# DM.net
KiCad netlist of a schematic drawn in Altium Designer
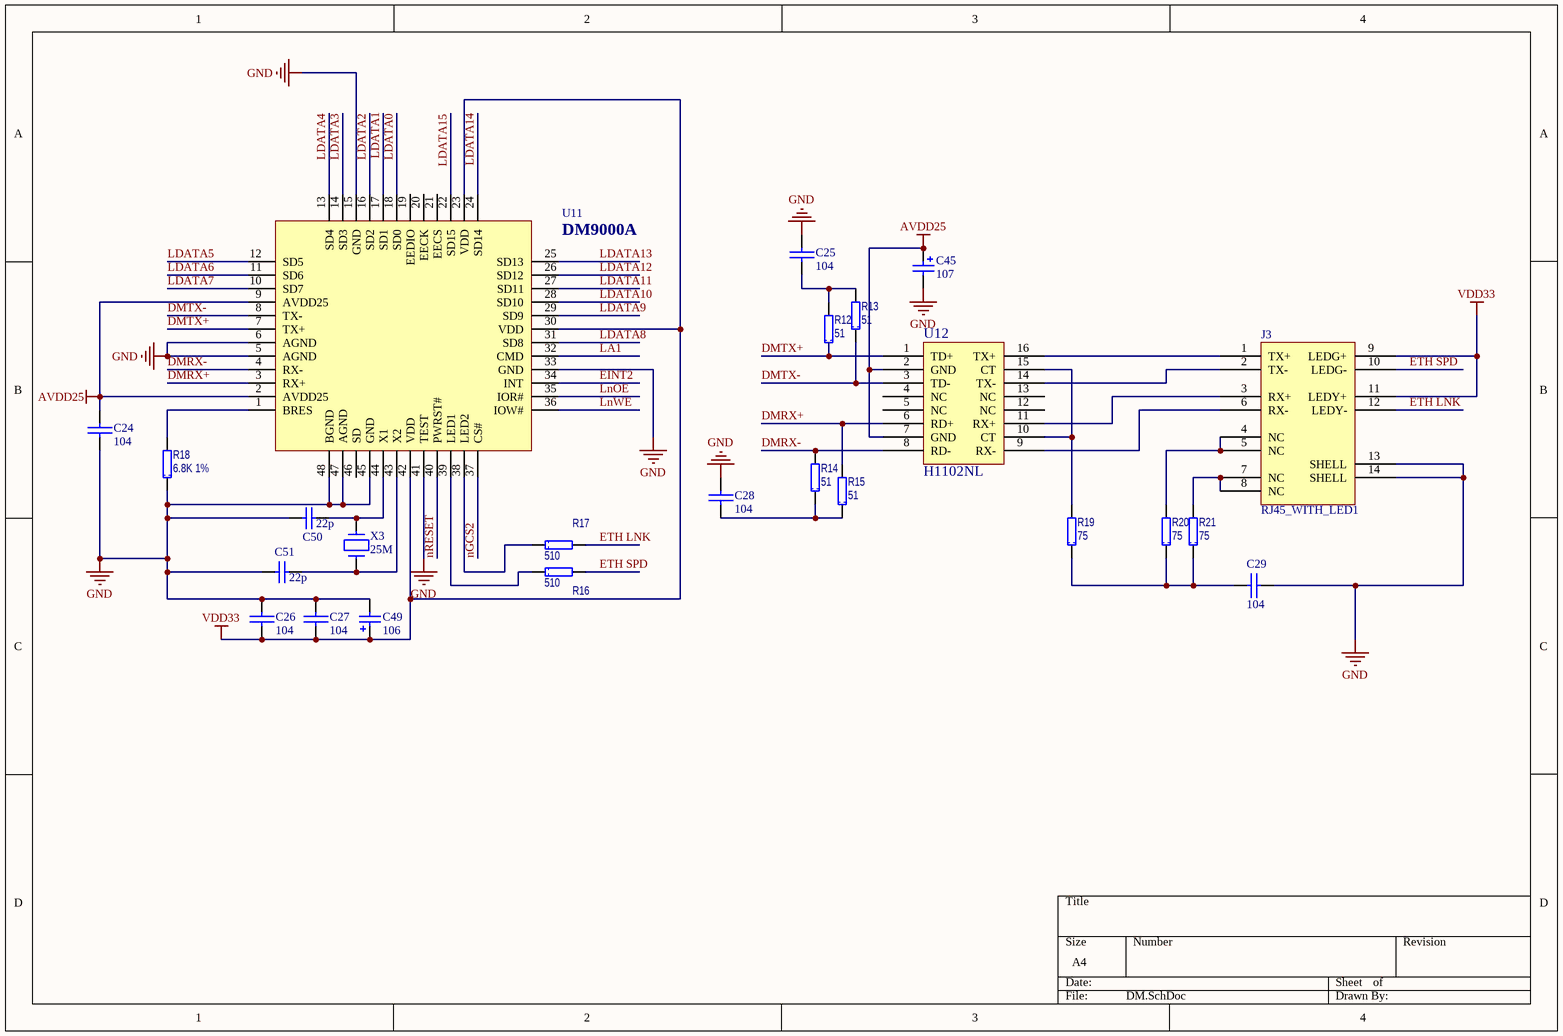
[diagram p0: DM.SchDoc]

(export (version "E")
  (design (tool "Eeschema 10.0.6"))
  (components
    (comp (ref "C24") (value "104") (footprint "0603A") (libsource (lib "ARM_DEMO") (part "CAP_3")))
    (comp (ref "C25")
      (value "104")
      (footprint "0603A")
      (description "Capacitor")
      (libsource (lib "ARM_DEMO") (part "CAP_2"))
    )
    (comp (ref "C26")
      (value "104")
      (footprint "A型钽电容")
      (description "Capacitor")
      (libsource (lib "ARM_DEMO") (part "CAP_1"))
    )
    (comp (ref "C27")
      (value "104")
      (footprint "A型钽电容")
      (description "Capacitor")
      (libsource (lib "ARM_DEMO") (part "CAP_1"))
    )
    (comp (ref "C28")
      (value "104")
      (footprint "0603A")
      (description "Capacitor")
      (libsource (lib "ARM_DEMO") (part "CAP_2"))
    )
    (comp (ref "C29")
      (value "104")
      (footprint "A型钽电容")
      (description "Capacitor")
      (libsource (lib "ARM_DEMO") (part "CAP_1"))
    )
    (comp (ref "C45")
      (value "107")
      (footprint "POLAR0.8")
      (description "Polarized Capacitor (Axial)")
      (fields (field (name "Comment") "Cap Pol2") (field (name "PUBLISHER") "Altium Limited"))
      (libsource (lib "Miscellaneous Devices") (part "Cap Pol2"))
    )
    (comp (ref "C49")
      (value "106")
      (footprint "POLAR0.8")
      (description "Polarized Capacitor (Axial)")
      (fields (field (name "Comment") "Cap Pol2") (field (name "PUBLISHER") "Altium Limited"))
      (libsource (lib "Miscellaneous Devices") (part "Cap Pol2"))
    )
    (comp (ref "C50")
      (value "22p")
      (footprint "3225")
      (description "Capacitor")
      (fields (field (name "Comment") "Cap") (field (name "PUBLISHER") "Altium Limited"))
      (libsource (lib "ARM_DEMO") (part "Cap"))
    )
    (comp (ref "C51")
      (value "22p")
      (footprint "3225")
      (description "Capacitor")
      (fields (field (name "Comment") "Cap") (field (name "PUBLISHER") "Altium Limited"))
      (libsource (lib "ARM_DEMO") (part "Cap"))
    )
    (comp (ref "J3")
      (value "RJ45_WITH_LED1")
      (footprint "RJ45")
      (libsource (lib "mySchlib") (part "RJ45_WITH_LED1"))
    )
    (comp (ref "R12") (value "51") (footprint "0603R") (libsource (lib "ARM_DEMO") (part "RES")))
    (comp (ref "R13") (value "51") (footprint "0603R") (libsource (lib "ARM_DEMO") (part "RES")))
    (comp (ref "R14") (value "51") (footprint "0603R") (libsource (lib "ARM_DEMO") (part "RES")))
    (comp (ref "R15") (value "51") (footprint "0603R") (libsource (lib "ARM_DEMO") (part "RES")))
    (comp (ref "R16") (value "510") (footprint "0603R") (libsource (lib "ARM_DEMO") (part "RES")))
    (comp (ref "R17") (value "510") (footprint "0603R") (libsource (lib "ARM_DEMO") (part "RES")))
    (comp (ref "R18") (value "6.8K 1%") (footprint "0603R") (libsource (lib "ARM_DEMO") (part "RES")))
    (comp (ref "R19") (value "75") (footprint "0603R") (libsource (lib "ARM_DEMO") (part "RES")))
    (comp (ref "R20") (value "75") (footprint "0603R") (libsource (lib "ARM_DEMO") (part "RES")))
    (comp (ref "R21") (value "75") (footprint "0603R") (libsource (lib "ARM_DEMO") (part "RES")))
    (comp (ref "U11")
      (value "DM9000A")
      (footprint "LQFP-48_M")
      (description "网络芯片")
      (libsource (lib "ARM_DEMO") (part "DM9000A"))
    )
    (comp (ref "U12") (value "H1102NL") (footprint "H1102") (libsource (lib "ARM_DEMO") (part "H1012")))
    (comp (ref "X3") (value "25M") (footprint "OSC2PR-1") (libsource (lib "ARM_DEMO") (part "CRYSTAL_2")))
  )
  (nets
    (net (code "1") (name "/DMRX+") (class "Default")
      (node (ref "R15") (pin "2") (pinfunction "2_2") (pintype "passive"))
      (node (ref "U11") (pin "3") (pinfunction "RX+_3") (pintype "passive"))
      (node (ref "U12") (pin "6") (pinfunction "RD+_6") (pintype "passive"))
    )
    (net (code "2") (name "/DMRX-") (class "Default")
      (node (ref "R14") (pin "2") (pinfunction "2_2") (pintype "passive"))
      (node (ref "U11") (pin "4") (pinfunction "RX-_4") (pintype "passive"))
      (node (ref "U12") (pin "8") (pinfunction "RD-_8") (pintype "passive"))
    )
    (net (code "3") (name "/DMTX+") (class "Default")
      (node (ref "R12") (pin "1") (pinfunction "1_1") (pintype "passive"))
      (node (ref "U11") (pin "7") (pinfunction "TX+_7") (pintype "passive"))
      (node (ref "U12") (pin "1") (pinfunction "TD+_1") (pintype "passive"))
    )
    (net (code "4") (name "/DMTX-") (class "Default")
      (node (ref "R13") (pin "1") (pinfunction "1_1") (pintype "passive"))
      (node (ref "U11") (pin "8") (pinfunction "TX-_8") (pintype "passive"))
      (node (ref "U12") (pin "3") (pinfunction "TD-_3") (pintype "passive"))
    )
    (net (code "5") (name "/EINT2") (class "Default")
      (node (ref "U11") (pin "34") (pinfunction "INT_34") (pintype "passive"))
    )
    (net (code "6") (name "/ETH LNK") (class "Default")
      (node (ref "J3") (pin "12") (pinfunction "LEDY-_12") (pintype "passive"))
      (node (ref "R17") (pin "2") (pinfunction "2_2") (pintype "passive"))
    )
    (net (code "7") (name "/ETH SPD") (class "Default")
      (node (ref "J3") (pin "10") (pinfunction "LEDG-_10") (pintype "passive"))
      (node (ref "R16") (pin "2") (pinfunction "2_2") (pintype "passive"))
    )
    (net (code "8") (name "/LA1") (class "Default")
      (node (ref "U11") (pin "32") (pinfunction "CMD_32") (pintype "passive"))
    )
    (net (code "9") (name "/LDATA0") (class "Default")
      (node (ref "U11") (pin "18") (pinfunction "SD0_18") (pintype "passive"))
    )
    (net (code "10") (name "/LDATA1") (class "Default")
      (node (ref "U11") (pin "17") (pinfunction "SD1_17") (pintype "passive"))
    )
    (net (code "11") (name "/LDATA2") (class "Default")
      (node (ref "U11") (pin "16") (pinfunction "SD2_16") (pintype "passive"))
    )
    (net (code "12") (name "/LDATA3") (class "Default")
      (node (ref "U11") (pin "14") (pinfunction "SD3_14") (pintype "passive"))
    )
    (net (code "13") (name "/LDATA4") (class "Default")
      (node (ref "U11") (pin "13") (pinfunction "SD4_13") (pintype "passive"))
    )
    (net (code "14") (name "/LDATA5") (class "Default")
      (node (ref "U11") (pin "12") (pinfunction "SD5_12") (pintype "passive"))
    )
    (net (code "15") (name "/LDATA6") (class "Default")
      (node (ref "U11") (pin "11") (pinfunction "SD6_11") (pintype "passive"))
    )
    (net (code "16") (name "/LDATA7") (class "Default")
      (node (ref "U11") (pin "10") (pinfunction "SD7_10") (pintype "passive"))
    )
    (net (code "17") (name "/LDATA8") (class "Default")
      (node (ref "U11") (pin "31") (pinfunction "SD8_31") (pintype "passive"))
    )
    (net (code "18") (name "/LDATA9") (class "Default")
      (node (ref "U11") (pin "29") (pinfunction "SD9_29") (pintype "passive"))
    )
    (net (code "19") (name "/LDATA10") (class "Default")
      (node (ref "U11") (pin "28") (pinfunction "SD10_28") (pintype "passive"))
    )
    (net (code "20") (name "/LDATA11") (class "Default")
      (node (ref "U11") (pin "27") (pinfunction "SD11_27") (pintype "passive"))
    )
    (net (code "21") (name "/LDATA12") (class "Default")
      (node (ref "U11") (pin "26") (pinfunction "SD12_26") (pintype "passive"))
    )
    (net (code "22") (name "/LDATA13") (class "Default")
      (node (ref "U11") (pin "25") (pinfunction "SD13_25") (pintype "passive"))
    )
    (net (code "23") (name "/LDATA14") (class "Default")
      (node (ref "U11") (pin "24") (pinfunction "SD14_24") (pintype "passive"))
    )
    (net (code "24") (name "/LDATA15") (class "Default")
      (node (ref "U11") (pin "22") (pinfunction "SD15_22") (pintype "passive"))
    )
    (net (code "25") (name "/LnOE") (class "Default")
      (node (ref "U11") (pin "35") (pinfunction "IOR#_35") (pintype "passive"))
    )
    (net (code "26") (name "/LnWE") (class "Default")
      (node (ref "U11") (pin "36") (pinfunction "IOW#_36") (pintype "passive"))
    )
    (net (code "27") (name "/nGCS2") (class "Default")
      (node (ref "U11") (pin "37") (pinfunction "CS#_37") (pintype "passive"))
    )
    (net (code "28") (name "/nRESET") (class "Default")
      (node (ref "U11") (pin "40") (pinfunction "PWRST#_40") (pintype "passive"))
    )
    (net (code "29") (name "AVDD25") (class "Default")
      (node (ref "C24") (pin "1") (pintype "passive"))
      (node (ref "C45") (pin "1") (pinfunction "1_1") (pintype "passive"))
      (node (ref "U11") (pin "2") (pinfunction "AVDD25_2") (pintype "passive"))
      (node (ref "U11") (pin "9") (pinfunction "AVDD25_9") (pintype "passive"))
      (node (ref "U12") (pin "2") (pinfunction "GND_2") (pintype "passive"))
      (node (ref "U12") (pin "7") (pinfunction "GND_7") (pintype "passive"))
    )
    (net (code "30") (name "GND") (class "Default")
      (node (ref "C24") (pin "2") (pintype "passive"))
      (node (ref "C25") (pin "1") (pinfunction "1_1") (pintype "passive"))
      (node (ref "C26") (pin "1") (pinfunction "1_1") (pintype "passive"))
      (node (ref "C27") (pin "1") (pinfunction "1_1") (pintype "passive"))
      (node (ref "C28") (pin "1") (pinfunction "1_1") (pintype "passive"))
      (node (ref "C29") (pin "2") (pinfunction "2_2") (pintype "passive"))
      (node (ref "C45") (pin "2") (pinfunction "2_2") (pintype "passive"))
      (node (ref "C49") (pin "2") (pinfunction "2_2") (pintype "passive"))
      (node (ref "C50") (pin "1") (pinfunction "1_1") (pintype "passive"))
      (node (ref "C51") (pin "1") (pinfunction "1_1") (pintype "passive"))
      (node (ref "J3") (pin "13") (pinfunction "SHELL_13") (pintype "passive"))
      (node (ref "J3") (pin "14") (pinfunction "SHELL_14") (pintype "passive"))
      (node (ref "R18") (pin "1") (pinfunction "1_1") (pintype "passive"))
      (node (ref "U11") (pin "15") (pinfunction "GND_15") (pintype "passive"))
      (node (ref "U11") (pin "33") (pinfunction "GND_33") (pintype "passive"))
      (node (ref "U11") (pin "41") (pinfunction "TEST_41") (pintype "passive"))
      (node (ref "U11") (pin "45") (pinfunction "GND_45") (pintype "passive"))
      (node (ref "U11") (pin "47") (pinfunction "AGND_47") (pintype "passive"))
      (node (ref "U11") (pin "48") (pinfunction "BGND_48") (pintype "passive"))
      (node (ref "U11") (pin "5") (pinfunction "AGND_5") (pintype "passive"))
      (node (ref "U11") (pin "6") (pinfunction "AGND_6") (pintype "passive"))
    )
    (net (code "31") (name "Net-(C25-Pad2)") (class "Default")
      (node (ref "C25") (pin "2") (pinfunction "2_2") (pintype "passive"))
      (node (ref "R12") (pin "2") (pinfunction "2_2") (pintype "passive"))
      (node (ref "R13") (pin "2") (pinfunction "2_2") (pintype "passive"))
    )
    (net (code "32") (name "Net-(C28-Pad2)") (class "Default")
      (node (ref "C28") (pin "2") (pinfunction "2_2") (pintype "passive"))
      (node (ref "R14") (pin "1") (pinfunction "1_1") (pintype "passive"))
      (node (ref "R15") (pin "1") (pinfunction "1_1") (pintype "passive"))
    )
    (net (code "33") (name "Net-(C29-Pad1)") (class "Default")
      (node (ref "C29") (pin "1") (pinfunction "1_1") (pintype "passive"))
      (node (ref "R19") (pin "1") (pinfunction "1_1") (pintype "passive"))
      (node (ref "R20") (pin "1") (pinfunction "1_1") (pintype "passive"))
      (node (ref "R21") (pin "1") (pinfunction "1_1") (pintype "passive"))
    )
    (net (code "34") (name "Net-(J3-NC-Pad4)") (class "Default")
      (node (ref "J3") (pin "4") (pinfunction "NC_4") (pintype "passive"))
      (node (ref "J3") (pin "5") (pinfunction "NC_5") (pintype "passive"))
      (node (ref "R20") (pin "2") (pinfunction "2_2") (pintype "passive"))
    )
    (net (code "35") (name "Net-(J3-NC-Pad7)") (class "Default")
      (node (ref "J3") (pin "7") (pinfunction "NC_7") (pintype "passive"))
      (node (ref "J3") (pin "8") (pinfunction "NC_8") (pintype "passive"))
      (node (ref "R21") (pin "2") (pinfunction "2_2") (pintype "passive"))
    )
    (net (code "36") (name "Net-(J3-RX+)") (class "Default")
      (node (ref "J3") (pin "3") (pinfunction "RX+_3") (pintype "passive"))
      (node (ref "U12") (pin "11") (pinfunction "RX+_11") (pintype "passive"))
    )
    (net (code "37") (name "Net-(J3-RX-)") (class "Default")
      (node (ref "J3") (pin "6") (pinfunction "RX-_6") (pintype "passive"))
      (node (ref "U12") (pin "9") (pinfunction "RX-_9") (pintype "passive"))
    )
    (net (code "38") (name "Net-(J3-TX+)") (class "Default")
      (node (ref "J3") (pin "1") (pinfunction "TX+_1") (pintype "passive"))
      (node (ref "U12") (pin "16") (pinfunction "TX+_16") (pintype "passive"))
    )
    (net (code "39") (name "Net-(J3-TX-)") (class "Default")
      (node (ref "J3") (pin "2") (pinfunction "TX-_2") (pintype "passive"))
      (node (ref "U12") (pin "14") (pinfunction "TX-_14") (pintype "passive"))
    )
    (net (code "40") (name "Net-(R19-Pad2)") (class "Default")
      (node (ref "R19") (pin "2") (pinfunction "2_2") (pintype "passive"))
      (node (ref "U12") (pin "10") (pinfunction "CT_10") (pintype "passive"))
      (node (ref "U12") (pin "15") (pinfunction "CT_15") (pintype "passive"))
    )
    (net (code "41") (name "Net-(U11-BRES)") (class "Default")
      (node (ref "R18") (pin "2") (pinfunction "2_2") (pintype "passive"))
      (node (ref "U11") (pin "1") (pinfunction "BRES_1") (pintype "passive"))
    )
    (net (code "42") (name "Net-(U11-LED1)") (class "Default")
      (node (ref "R16") (pin "1") (pinfunction "1_1") (pintype "passive"))
      (node (ref "U11") (pin "39") (pinfunction "LED1_39") (pintype "passive"))
    )
    (net (code "43") (name "Net-(U11-LED2)") (class "Default")
      (node (ref "R17") (pin "1") (pinfunction "1_1") (pintype "passive"))
      (node (ref "U11") (pin "38") (pinfunction "LED2_38") (pintype "passive"))
    )
    (net (code "44") (name "Net-(U11-X1)") (class "Default")
      (node (ref "C50") (pin "2") (pinfunction "2_2") (pintype "passive"))
      (node (ref "U11") (pin "44") (pinfunction "X1_44") (pintype "passive"))
      (node (ref "X3") (pin "2") (pintype "passive"))
    )
    (net (code "45") (name "Net-(U11-X2)") (class "Default")
      (node (ref "C51") (pin "2") (pinfunction "2_2") (pintype "passive"))
      (node (ref "U11") (pin "43") (pinfunction "X2_43") (pintype "passive"))
      (node (ref "X3") (pin "1") (pintype "passive"))
    )
    (net (code "46") (name "VDD33") (class "Default")
      (node (ref "C26") (pin "2") (pinfunction "2_2") (pintype "passive"))
      (node (ref "C27") (pin "2") (pinfunction "2_2") (pintype "passive"))
      (node (ref "C49") (pin "1") (pinfunction "1_1") (pintype "passive"))
      (node (ref "J3") (pin "11") (pinfunction "LEDY+_11") (pintype "passive"))
      (node (ref "J3") (pin "9") (pinfunction "LEDG+_9") (pintype "passive"))
      (node (ref "U11") (pin "23") (pinfunction "VDD_23") (pintype "passive"))
      (node (ref "U11") (pin "30") (pinfunction "VDD_30") (pintype "passive"))
      (node (ref "U11") (pin "42") (pinfunction "VDD_42") (pintype "passive"))
    )
    (net (code "47") (name "unconnected-(U11-EECK-Pad20)") (class "Default")
      (node (ref "U11") (pin "20") (pinfunction "EECK_20") (pintype "passive"))
    )
    (net (code "48") (name "unconnected-(U11-EECS-Pad21)") (class "Default")
      (node (ref "U11") (pin "21") (pinfunction "EECS_21") (pintype "passive"))
    )
    (net (code "49") (name "unconnected-(U11-EEDIO-Pad19)") (class "Default")
      (node (ref "U11") (pin "19") (pinfunction "EEDIO_19") (pintype "passive"))
    )
    (net (code "50") (name "unconnected-(U11-SD-Pad46)") (class "Default")
      (node (ref "U11") (pin "46") (pinfunction "SD_46") (pintype "passive"))
    )
    (net (code "51") (name "unconnected-(U12-NC-Pad4)") (class "Default")
      (node (ref "U12") (pin "4") (pinfunction "NC_4") (pintype "passive"))
    )
    (net (code "52") (name "unconnected-(U12-NC-Pad5)") (class "Default")
      (node (ref "U12") (pin "5") (pinfunction "NC_5") (pintype "passive"))
    )
    (net (code "53") (name "unconnected-(U12-NC-Pad12)") (class "Default")
      (node (ref "U12") (pin "12") (pinfunction "NC_12") (pintype "passive"))
    )
    (net (code "54") (name "unconnected-(U12-NC-Pad13)") (class "Default")
      (node (ref "U12") (pin "13") (pinfunction "NC_13") (pintype "passive"))
    )
  )
)
